# solar_cell.net
KiCad netlist of a schematic drawn in Altium Designer
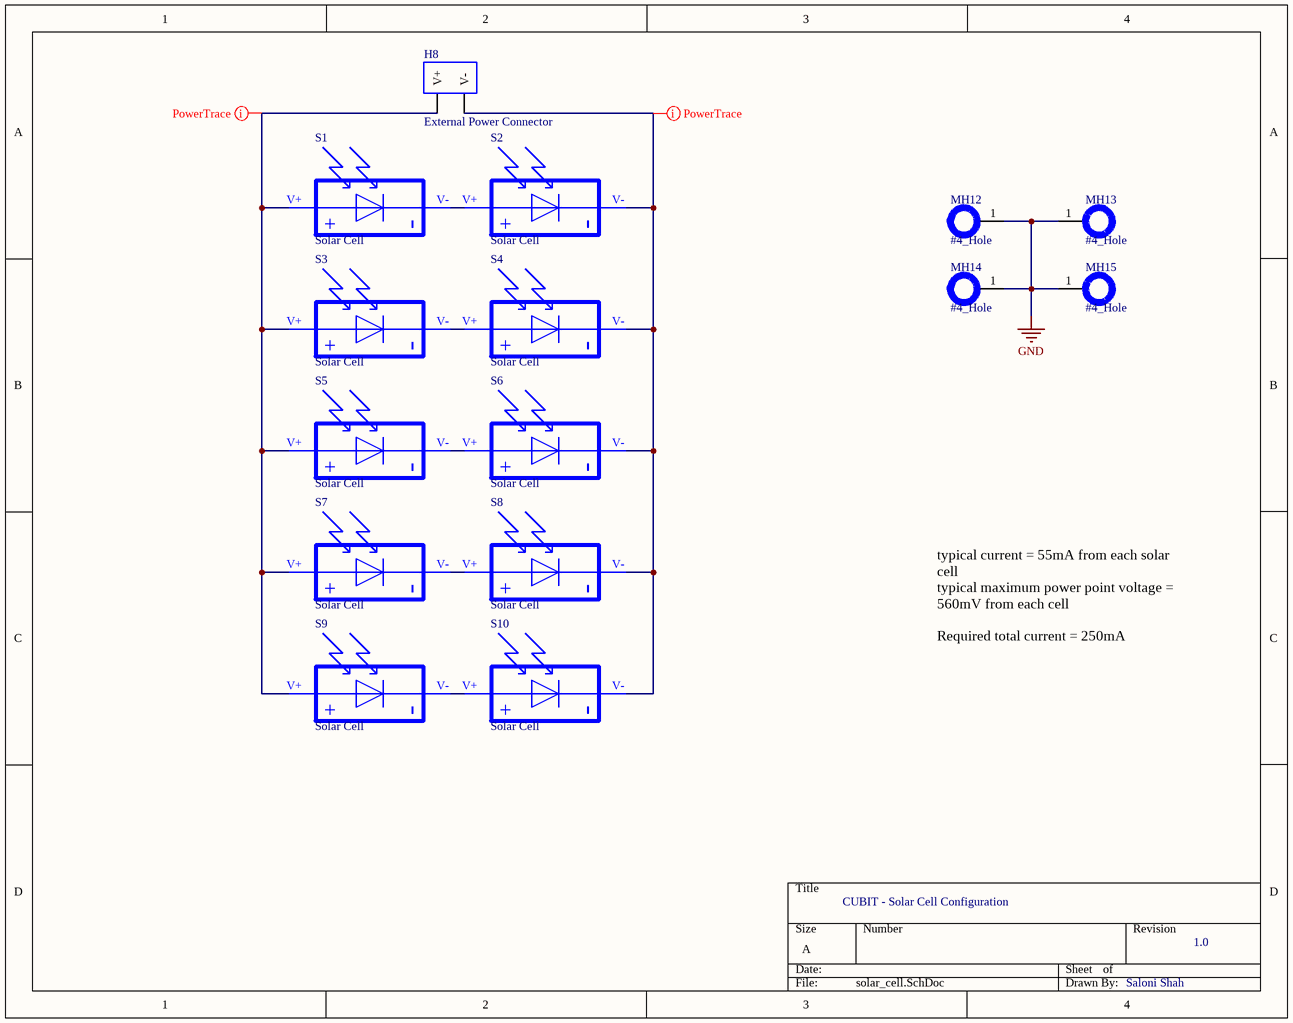
[diagram p0: solar_cell.SchDoc]

(export (version "E")
  (design (tool "Eeschema 10.0.6"))
  (components
    (comp (ref "H8")
      (value "External Power Connector")
      (footprint "LPEDT_proj_lib:2_PIN_100mil")
      (libsource (lib "LPEDT_proj_lib") (part "ext_pwr_conn"))
    )
    (comp (ref "MH12")
      (value "#4_Hole")
      (footprint "LPEDT_proj_lib:HOLE_#4")
      (libsource (lib "LPEDT_proj_lib") (part "Mechanical_Hole"))
    )
    (comp (ref "MH13")
      (value "#4_Hole")
      (footprint "LPEDT_proj_lib:HOLE_#4")
      (libsource (lib "LPEDT_proj_lib") (part "Mechanical_Hole"))
    )
    (comp (ref "MH14")
      (value "#4_Hole")
      (footprint "LPEDT_proj_lib:HOLE_#4")
      (libsource (lib "LPEDT_proj_lib") (part "Mechanical_Hole"))
    )
    (comp (ref "MH15")
      (value "#4_Hole")
      (footprint "LPEDT_proj_lib:HOLE_#4")
      (libsource (lib "LPEDT_proj_lib") (part "Mechanical_Hole"))
    )
    (comp (ref "S1")
      (value "Solar Cell")
      (footprint "KXOB25-14X1F")
      (description "MONOCRYS SOLAR CELL 30.7MW 690MV")
      (fields (field (name "MP") "KXOB25-14X1F") (field (name "MF") "ANYSOLAR Ltd"))
      (libsource (lib "LPEDT_proj_lib") (part "KXOB25-14X1F"))
    )
    (comp (ref "S2")
      (value "Solar Cell")
      (footprint "KXOB25-14X1F")
      (description "MONOCRYS SOLAR CELL 30.7MW 690MV")
      (fields (field (name "MP") "KXOB25-14X1F") (field (name "MF") "ANYSOLAR Ltd"))
      (libsource (lib "LPEDT_proj_lib") (part "KXOB25-14X1F"))
    )
    (comp (ref "S3")
      (value "Solar Cell")
      (footprint "KXOB25-14X1F")
      (description "MONOCRYS SOLAR CELL 30.7MW 690MV")
      (fields (field (name "MP") "KXOB25-14X1F") (field (name "MF") "ANYSOLAR Ltd"))
      (libsource (lib "LPEDT_proj_lib") (part "KXOB25-14X1F"))
    )
    (comp (ref "S4")
      (value "Solar Cell")
      (footprint "KXOB25-14X1F")
      (description "MONOCRYS SOLAR CELL 30.7MW 690MV")
      (fields (field (name "MP") "KXOB25-14X1F") (field (name "MF") "ANYSOLAR Ltd"))
      (libsource (lib "LPEDT_proj_lib") (part "KXOB25-14X1F"))
    )
    (comp (ref "S5")
      (value "Solar Cell")
      (footprint "KXOB25-14X1F")
      (description "MONOCRYS SOLAR CELL 30.7MW 690MV")
      (fields (field (name "MP") "KXOB25-14X1F") (field (name "MF") "ANYSOLAR Ltd"))
      (libsource (lib "LPEDT_proj_lib") (part "KXOB25-14X1F"))
    )
    (comp (ref "S6")
      (value "Solar Cell")
      (footprint "KXOB25-14X1F")
      (description "MONOCRYS SOLAR CELL 30.7MW 690MV")
      (fields (field (name "MP") "KXOB25-14X1F") (field (name "MF") "ANYSOLAR Ltd"))
      (libsource (lib "LPEDT_proj_lib") (part "KXOB25-14X1F"))
    )
    (comp (ref "S7")
      (value "Solar Cell")
      (footprint "KXOB25-14X1F")
      (description "MONOCRYS SOLAR CELL 30.7MW 690MV")
      (fields (field (name "MP") "KXOB25-14X1F") (field (name "MF") "ANYSOLAR Ltd"))
      (libsource (lib "LPEDT_proj_lib") (part "KXOB25-14X1F"))
    )
    (comp (ref "S8")
      (value "Solar Cell")
      (footprint "KXOB25-14X1F")
      (description "MONOCRYS SOLAR CELL 30.7MW 690MV")
      (fields (field (name "MP") "KXOB25-14X1F") (field (name "MF") "ANYSOLAR Ltd"))
      (libsource (lib "LPEDT_proj_lib") (part "KXOB25-14X1F"))
    )
    (comp (ref "S9")
      (value "Solar Cell")
      (footprint "KXOB25-14X1F")
      (description "MONOCRYS SOLAR CELL 30.7MW 690MV")
      (fields (field (name "MP") "KXOB25-14X1F") (field (name "MF") "ANYSOLAR Ltd"))
      (libsource (lib "LPEDT_proj_lib") (part "KXOB25-14X1F"))
    )
    (comp (ref "S10")
      (value "Solar Cell")
      (footprint "KXOB25-14X1F")
      (description "MONOCRYS SOLAR CELL 30.7MW 690MV")
      (fields (field (name "MP") "KXOB25-14X1F") (field (name "MF") "ANYSOLAR Ltd"))
      (libsource (lib "LPEDT_proj_lib") (part "KXOB25-14X1F"))
    )
  )
  (nets
    (net (code "1") (name "GND") (class "Default")
      (node (ref "MH12") (pin "1") (pinfunction "1_1") (pintype "passive"))
      (node (ref "MH13") (pin "1") (pinfunction "1_1") (pintype "passive"))
      (node (ref "MH14") (pin "1") (pinfunction "1_1") (pintype "passive"))
      (node (ref "MH15") (pin "1") (pinfunction "1_1") (pintype "passive"))
    )
    (net (code "2") (name "Net-(H8-V+)") (class "Default")
      (node (ref "H8") (pin "1") (pinfunction "V+_1") (pintype "passive"))
      (node (ref "S1") (pin "V+") (pintype "power_in"))
      (node (ref "S3") (pin "V+") (pintype "power_in"))
      (node (ref "S5") (pin "V+") (pintype "power_in"))
      (node (ref "S7") (pin "V+") (pintype "power_in"))
      (node (ref "S9") (pin "V+") (pintype "power_in"))
    )
    (net (code "3") (name "Net-(H8-V-)") (class "Default")
      (node (ref "H8") (pin "2") (pinfunction "V-_2") (pintype "passive"))
      (node (ref "S10") (pin "V-") (pintype "power_in"))
      (node (ref "S2") (pin "V-") (pintype "power_in"))
      (node (ref "S4") (pin "V-") (pintype "power_in"))
      (node (ref "S6") (pin "V-") (pintype "power_in"))
      (node (ref "S8") (pin "V-") (pintype "power_in"))
    )
    (net (code "4") (name "Net-(S1-PadV-)") (class "Default")
      (node (ref "S1") (pin "V-") (pintype "power_in"))
      (node (ref "S2") (pin "V+") (pintype "power_in"))
    )
    (net (code "5") (name "Net-(S3-PadV-)") (class "Default")
      (node (ref "S3") (pin "V-") (pintype "power_in"))
      (node (ref "S4") (pin "V+") (pintype "power_in"))
    )
    (net (code "6") (name "Net-(S5-PadV-)") (class "Default")
      (node (ref "S5") (pin "V-") (pintype "power_in"))
      (node (ref "S6") (pin "V+") (pintype "power_in"))
    )
    (net (code "7") (name "Net-(S7-PadV-)") (class "Default")
      (node (ref "S7") (pin "V-") (pintype "power_in"))
      (node (ref "S8") (pin "V+") (pintype "power_in"))
    )
    (net (code "8") (name "Net-(S10-PadV+)") (class "Default")
      (node (ref "S10") (pin "V+") (pintype "power_in"))
      (node (ref "S9") (pin "V-") (pintype "power_in"))
    )
  )
)
